# Slave.net
KiCad netlist of a schematic drawn in Altium Designer
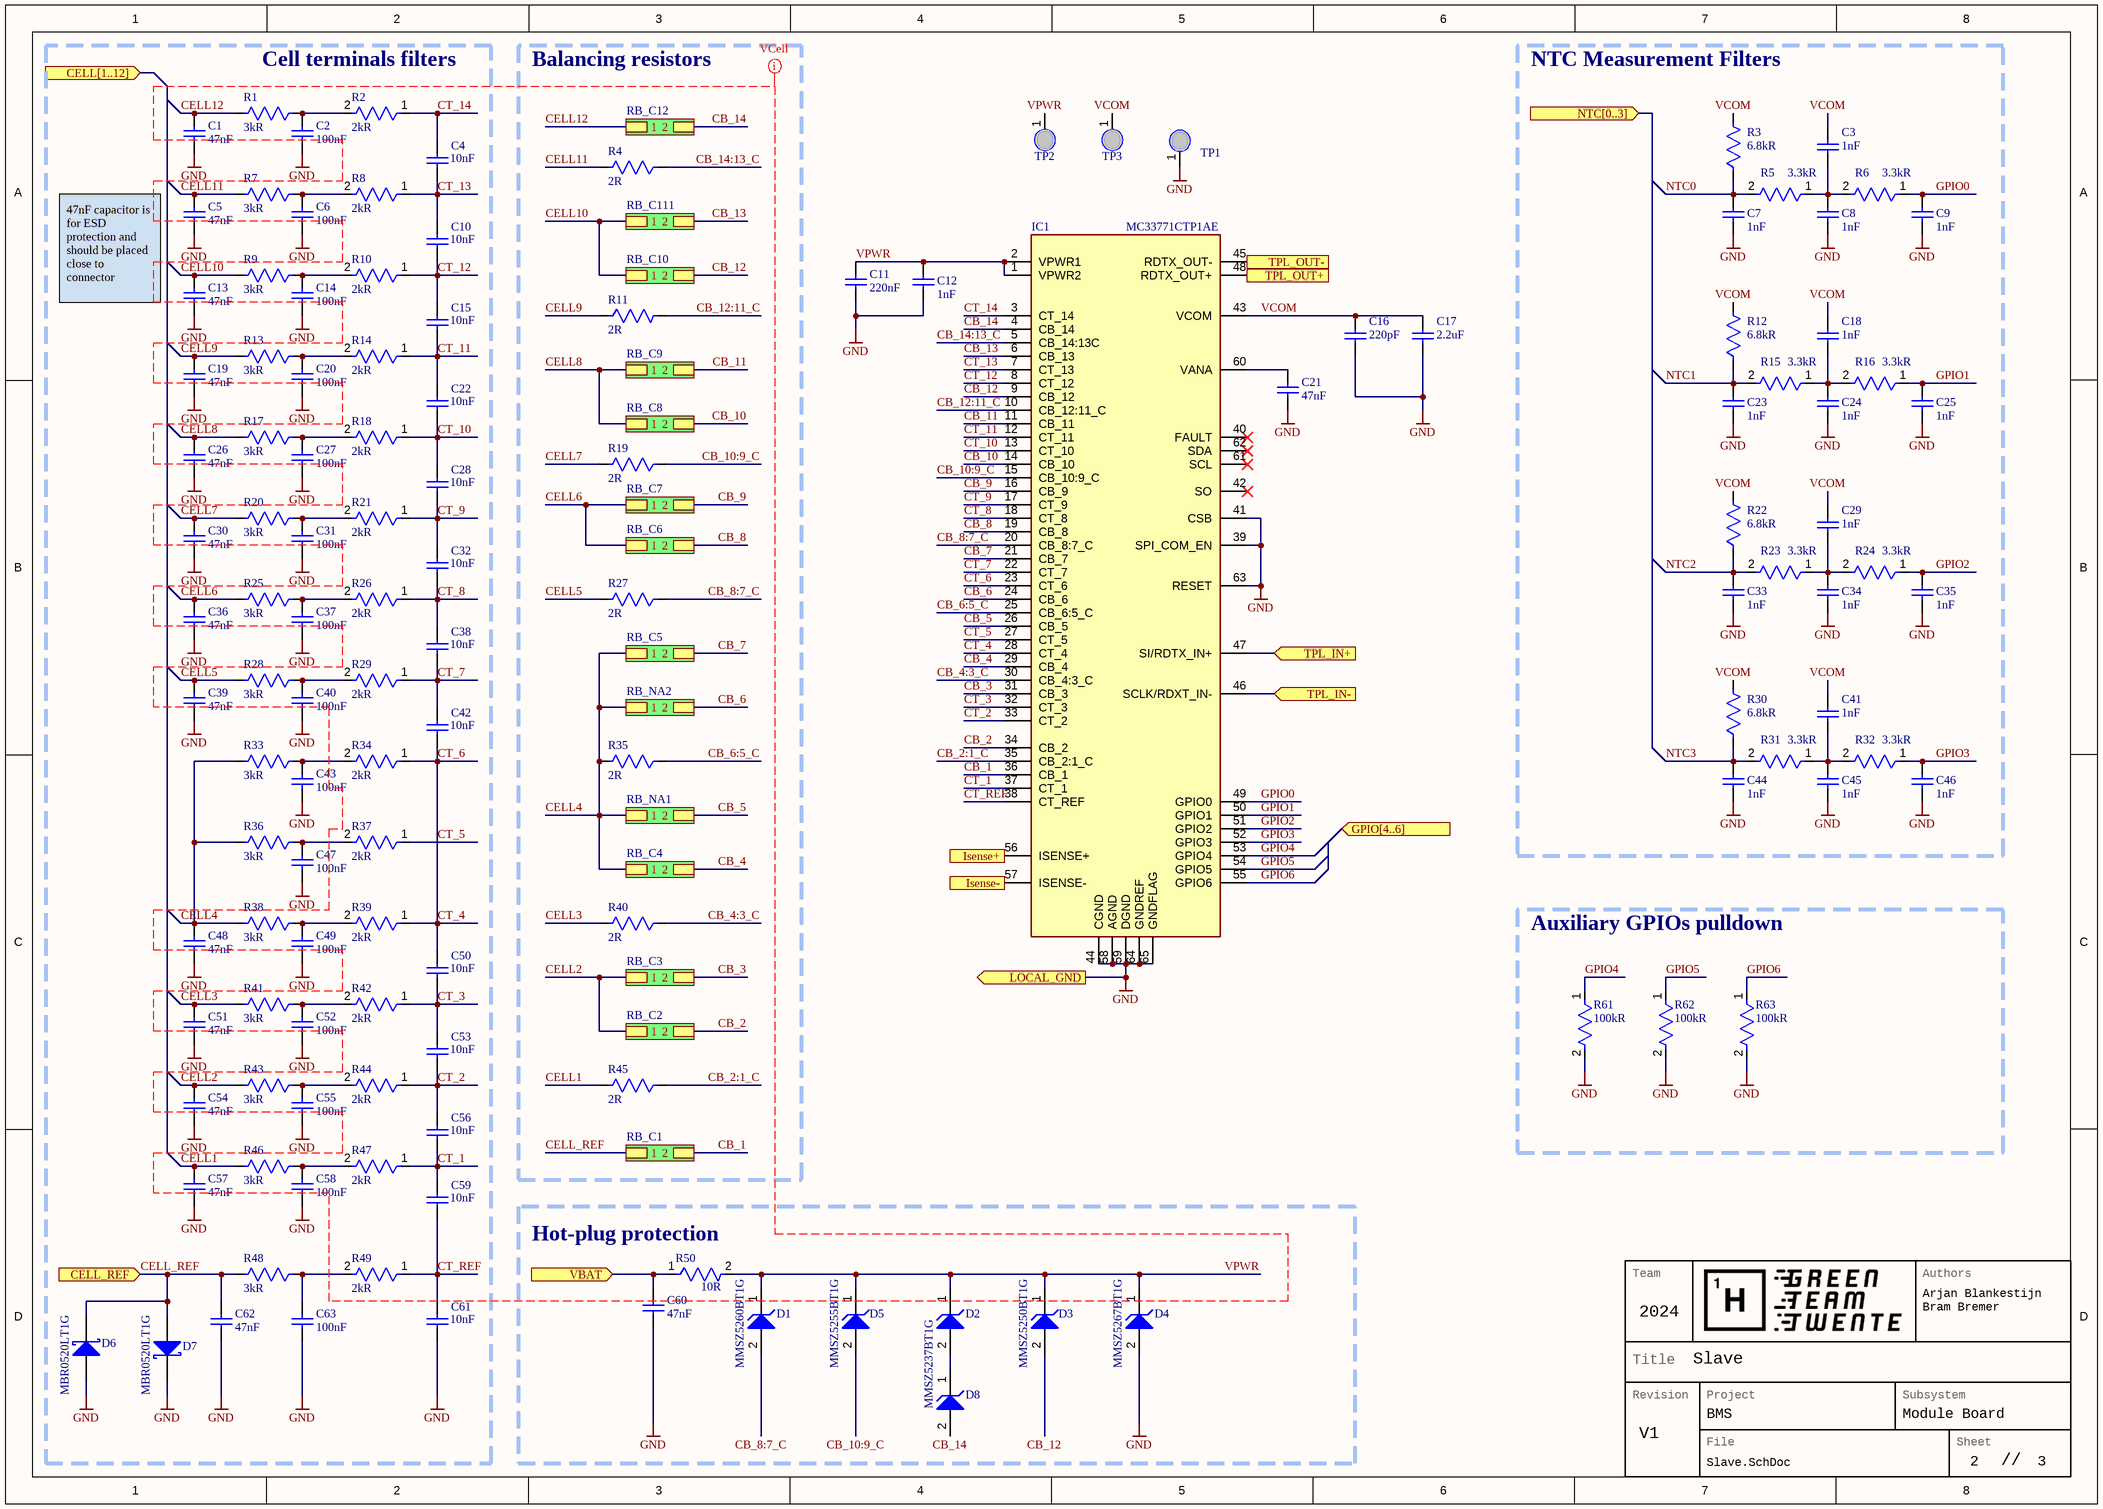
[diagram p0: Slave.SchDoc]

(export (version "E")
  (design (tool "Eeschema 10.0.6"))
  (components
    (comp (ref "C1")
      (value "47nF")
      (footprint "WCAP-CSGP_0603_L1.6W0.8H0.8_Reflow")
      (description "GTT Standard 0603 non-polarized capacitor")
      (fields (field (name "TOLERANCE") "5%") (field (name "JLCPCB PART #") "C1622"))
      (libsource (lib "Green Team Twente") (part "CAP_NONPOL_GENERIC"))
    )
    (comp (ref "C2")
      (value "100nF")
      (footprint "WCAP-CSGP_0603_L1.6W0.8H0.8_Reflow")
      (description "GTT Standard 0603 non-polarized capacitor")
      (fields (field (name "TOLERANCE") "5%") (field (name "JLCPCB PART #") "C14663"))
      (libsource (lib "Green Team Twente") (part "CAP_NONPOL_GENERIC"))
    )
    (comp (ref "C3")
      (value "1nF")
      (footprint "WCAP-CSGP_0402_L1W0.5H0.5")
      (description "GTT Standard 0402 non-polarized capacitor")
      (fields (field (name "JLCPCB PART #") "C1523") (field (name "Comment") "CAP 0402 1nF X7R"))
      (libsource (lib "Green Team Twente") (part "CAP_NONPOL_GENERIC"))
    )
    (comp (ref "C4")
      (value "10nF")
      (footprint "WCAP-CSGP_0402_L1W0.5H0.5")
      (description "GTT Standard 0402 non-polarized capacitor")
      (fields (field (name "JLCPCB PART #") "C15195") (field (name "Comment") "CAP 0402 10nF X7R"))
      (libsource (lib "Green Team Twente") (part "CAP_NONPOL_GENERIC"))
    )
    (comp (ref "C5")
      (value "47nF")
      (footprint "WCAP-CSGP_0603_L1.6W0.8H0.8_Reflow")
      (description "GTT Standard 0603 non-polarized capacitor")
      (fields (field (name "TOLERANCE") "5%") (field (name "JLCPCB PART #") "C1622"))
      (libsource (lib "Green Team Twente") (part "CAP_NONPOL_GENERIC"))
    )
    (comp (ref "C6")
      (value "100nF")
      (footprint "WCAP-CSGP_0603_L1.6W0.8H0.8_Reflow")
      (description "GTT Standard 0603 non-polarized capacitor")
      (fields (field (name "TOLERANCE") "5%") (field (name "JLCPCB PART #") "C14663"))
      (libsource (lib "Green Team Twente") (part "CAP_NONPOL_GENERIC"))
    )
    (comp (ref "C7")
      (value "1nF")
      (footprint "WCAP-CSGP_0402_L1W0.5H0.5")
      (description "GTT Standard 0402 non-polarized capacitor")
      (fields (field (name "JLCPCB PART #") "C1523") (field (name "Comment") "CAP 0402 1nF X7R"))
      (libsource (lib "Green Team Twente") (part "CAP_NONPOL_GENERIC"))
    )
    (comp (ref "C8")
      (value "1nF")
      (footprint "WCAP-CSGP_0402_L1W0.5H0.5")
      (description "GTT Standard 0402 non-polarized capacitor")
      (fields (field (name "JLCPCB PART #") "C1523") (field (name "Comment") "CAP 0402 1nF X7R"))
      (libsource (lib "Green Team Twente") (part "CAP_NONPOL_GENERIC"))
    )
    (comp (ref "C9")
      (value "1nF")
      (footprint "WCAP-CSGP_0402_L1W0.5H0.5")
      (description "GTT Standard 0402 non-polarized capacitor")
      (fields (field (name "JLCPCB PART #") "C1523") (field (name "Comment") "CAP 0402 1nF X7R"))
      (libsource (lib "Green Team Twente") (part "CAP_NONPOL_GENERIC"))
    )
    (comp (ref "C10")
      (value "10nF")
      (footprint "WCAP-CSGP_0402_L1W0.5H0.5")
      (description "GTT Standard 0402 non-polarized capacitor")
      (fields (field (name "JLCPCB PART #") "C15195") (field (name "Comment") "CAP 0402 10nF X7R"))
      (libsource (lib "Green Team Twente") (part "CAP_NONPOL_GENERIC"))
    )
    (comp (ref "C11")
      (value "220nF")
      (footprint "WCAP-CSGP_0603_L1.6W0.8H0.8_Reflow")
      (description "GTT Standard 0603 non-polarized capacitor")
      (fields (field (name "TOLERANCE") "5%") (field (name "JLCPCB PART #") "C21120"))
      (libsource (lib "Green Team Twente") (part "CAP_NONPOL_GENERIC"))
    )
    (comp (ref "C12")
      (value "1nF")
      (footprint "WCAP-CSGP_0402_L1W0.5H0.5")
      (description "GTT Standard 0402 non-polarized capacitor")
      (fields (field (name "JLCPCB PART #") "C1523") (field (name "Comment") "CAP 0402 1nF X7R"))
      (libsource (lib "Green Team Twente") (part "CAP_NONPOL_GENERIC"))
    )
    (comp (ref "C13")
      (value "47nF")
      (footprint "WCAP-CSGP_0603_L1.6W0.8H0.8_Reflow")
      (description "GTT Standard 0603 non-polarized capacitor")
      (fields (field (name "TOLERANCE") "5%") (field (name "JLCPCB PART #") "C1622"))
      (libsource (lib "Green Team Twente") (part "CAP_NONPOL_GENERIC"))
    )
    (comp (ref "C14")
      (value "100nF")
      (footprint "WCAP-CSGP_0603_L1.6W0.8H0.8_Reflow")
      (description "GTT Standard 0603 non-polarized capacitor")
      (fields (field (name "TOLERANCE") "5%") (field (name "JLCPCB PART #") "C14663"))
      (libsource (lib "Green Team Twente") (part "CAP_NONPOL_GENERIC"))
    )
    (comp (ref "C15")
      (value "10nF")
      (footprint "WCAP-CSGP_0402_L1W0.5H0.5")
      (description "GTT Standard 0402 non-polarized capacitor")
      (fields (field (name "JLCPCB PART #") "C15195") (field (name "Comment") "CAP 0402 10nF X7R"))
      (libsource (lib "Green Team Twente") (part "CAP_NONPOL_GENERIC"))
    )
    (comp (ref "C16")
      (value "220pF")
      (footprint "WCAP-CSGP_0402_L1W0.5H0.5")
      (description "GTT Standard 0402 non-polarized capacitor")
      (fields (field (name "JLCPCB PART #") "C1530") (field (name "Comment") "CAP 0402 220pF X7R"))
      (libsource (lib "Green Team Twente") (part "CAP_NONPOL_GENERIC"))
    )
    (comp (ref "C17")
      (value "2.2uF")
      (footprint "WCAP-CSGP_0603_L1.6W0.8H0.8_Reflow")
      (description "GTT Standard 0603 non-polarized capacitor")
      (fields (field (name "TOLERANCE") "5%") (field (name "JLCPCB PART #") "C23630"))
      (libsource (lib "Green Team Twente") (part "CAP_NONPOL_GENERIC"))
    )
    (comp (ref "C18")
      (value "1nF")
      (footprint "WCAP-CSGP_0402_L1W0.5H0.5")
      (description "GTT Standard 0402 non-polarized capacitor")
      (fields (field (name "JLCPCB PART #") "C1523") (field (name "Comment") "CAP 0402 1nF X7R"))
      (libsource (lib "Green Team Twente") (part "CAP_NONPOL_GENERIC"))
    )
    (comp (ref "C19")
      (value "47nF")
      (footprint "WCAP-CSGP_0603_L1.6W0.8H0.8_Reflow")
      (description "GTT Standard 0603 non-polarized capacitor")
      (fields (field (name "TOLERANCE") "5%") (field (name "JLCPCB PART #") "C1622"))
      (libsource (lib "Green Team Twente") (part "CAP_NONPOL_GENERIC"))
    )
    (comp (ref "C20")
      (value "100nF")
      (footprint "WCAP-CSGP_0603_L1.6W0.8H0.8_Reflow")
      (description "GTT Standard 0603 non-polarized capacitor")
      (fields (field (name "TOLERANCE") "5%") (field (name "JLCPCB PART #") "C14663"))
      (libsource (lib "Green Team Twente") (part "CAP_NONPOL_GENERIC"))
    )
    (comp (ref "C21")
      (value "47nF")
      (footprint "WCAP-CSGP_0603_L1.6W0.8H0.8_Reflow")
      (description "GTT Standard 0603 non-polarized capacitor")
      (fields (field (name "TOLERANCE") "5%") (field (name "JLCPCB PART #") "C1622"))
      (libsource (lib "Green Team Twente") (part "CAP_NONPOL_GENERIC"))
    )
    (comp (ref "C22")
      (value "10nF")
      (footprint "WCAP-CSGP_0402_L1W0.5H0.5")
      (description "GTT Standard 0402 non-polarized capacitor")
      (fields (field (name "JLCPCB PART #") "C15195") (field (name "Comment") "CAP 0402 10nF X7R"))
      (libsource (lib "Green Team Twente") (part "CAP_NONPOL_GENERIC"))
    )
    (comp (ref "C23")
      (value "1nF")
      (footprint "WCAP-CSGP_0402_L1W0.5H0.5")
      (description "GTT Standard 0402 non-polarized capacitor")
      (fields (field (name "JLCPCB PART #") "C1523") (field (name "Comment") "CAP 0402 1nF X7R"))
      (libsource (lib "Green Team Twente") (part "CAP_NONPOL_GENERIC"))
    )
    (comp (ref "C24")
      (value "1nF")
      (footprint "WCAP-CSGP_0402_L1W0.5H0.5")
      (description "GTT Standard 0402 non-polarized capacitor")
      (fields (field (name "JLCPCB PART #") "C1523") (field (name "Comment") "CAP 0402 1nF X7R"))
      (libsource (lib "Green Team Twente") (part "CAP_NONPOL_GENERIC"))
    )
    (comp (ref "C25")
      (value "1nF")
      (footprint "WCAP-CSGP_0402_L1W0.5H0.5")
      (description "GTT Standard 0402 non-polarized capacitor")
      (fields (field (name "JLCPCB PART #") "C1523") (field (name "Comment") "CAP 0402 1nF X7R"))
      (libsource (lib "Green Team Twente") (part "CAP_NONPOL_GENERIC"))
    )
    (comp (ref "C26")
      (value "47nF")
      (footprint "WCAP-CSGP_0603_L1.6W0.8H0.8_Reflow")
      (description "GTT Standard 0603 non-polarized capacitor")
      (fields (field (name "TOLERANCE") "5%") (field (name "JLCPCB PART #") "C1622"))
      (libsource (lib "Green Team Twente") (part "CAP_NONPOL_GENERIC"))
    )
    (comp (ref "C27")
      (value "100nF")
      (footprint "WCAP-CSGP_0603_L1.6W0.8H0.8_Reflow")
      (description "GTT Standard 0603 non-polarized capacitor")
      (fields (field (name "TOLERANCE") "5%") (field (name "JLCPCB PART #") "C14663"))
      (libsource (lib "Green Team Twente") (part "CAP_NONPOL_GENERIC"))
    )
    (comp (ref "C28")
      (value "10nF")
      (footprint "WCAP-CSGP_0402_L1W0.5H0.5")
      (description "GTT Standard 0402 non-polarized capacitor")
      (fields (field (name "JLCPCB PART #") "C15195") (field (name "Comment") "CAP 0402 10nF X7R"))
      (libsource (lib "Green Team Twente") (part "CAP_NONPOL_GENERIC"))
    )
    (comp (ref "C29")
      (value "1nF")
      (footprint "WCAP-CSGP_0402_L1W0.5H0.5")
      (description "GTT Standard 0402 non-polarized capacitor")
      (fields (field (name "JLCPCB PART #") "C1523") (field (name "Comment") "CAP 0402 1nF X7R"))
      (libsource (lib "Green Team Twente") (part "CAP_NONPOL_GENERIC"))
    )
    (comp (ref "C30")
      (value "47nF")
      (footprint "WCAP-CSGP_0603_L1.6W0.8H0.8_Reflow")
      (description "GTT Standard 0603 non-polarized capacitor")
      (fields (field (name "TOLERANCE") "5%") (field (name "JLCPCB PART #") "C1622"))
      (libsource (lib "Green Team Twente") (part "CAP_NONPOL_GENERIC"))
    )
    (comp (ref "C31")
      (value "100nF")
      (footprint "WCAP-CSGP_0603_L1.6W0.8H0.8_Reflow")
      (description "GTT Standard 0603 non-polarized capacitor")
      (fields (field (name "TOLERANCE") "5%") (field (name "JLCPCB PART #") "C14663"))
      (libsource (lib "Green Team Twente") (part "CAP_NONPOL_GENERIC"))
    )
    (comp (ref "C32")
      (value "10nF")
      (footprint "WCAP-CSGP_0402_L1W0.5H0.5")
      (description "GTT Standard 0402 non-polarized capacitor")
      (fields (field (name "JLCPCB PART #") "C15195") (field (name "Comment") "CAP 0402 10nF X7R"))
      (libsource (lib "Green Team Twente") (part "CAP_NONPOL_GENERIC"))
    )
    (comp (ref "C33")
      (value "1nF")
      (footprint "WCAP-CSGP_0402_L1W0.5H0.5")
      (description "GTT Standard 0402 non-polarized capacitor")
      (fields (field (name "JLCPCB PART #") "C1523") (field (name "Comment") "CAP 0402 1nF X7R"))
      (libsource (lib "Green Team Twente") (part "CAP_NONPOL_GENERIC"))
    )
    (comp (ref "C34")
      (value "1nF")
      (footprint "WCAP-CSGP_0402_L1W0.5H0.5")
      (description "GTT Standard 0402 non-polarized capacitor")
      (fields (field (name "JLCPCB PART #") "C1523") (field (name "Comment") "CAP 0402 1nF X7R"))
      (libsource (lib "Green Team Twente") (part "CAP_NONPOL_GENERIC"))
    )
    (comp (ref "C35")
      (value "1nF")
      (footprint "WCAP-CSGP_0402_L1W0.5H0.5")
      (description "GTT Standard 0402 non-polarized capacitor")
      (fields (field (name "JLCPCB PART #") "C1523") (field (name "Comment") "CAP 0402 1nF X7R"))
      (libsource (lib "Green Team Twente") (part "CAP_NONPOL_GENERIC"))
    )
    (comp (ref "C36")
      (value "47nF")
      (footprint "WCAP-CSGP_0603_L1.6W0.8H0.8_Reflow")
      (description "GTT Standard 0603 non-polarized capacitor")
      (fields (field (name "TOLERANCE") "5%") (field (name "JLCPCB PART #") "C1622"))
      (libsource (lib "Green Team Twente") (part "CAP_NONPOL_GENERIC"))
    )
    (comp (ref "C37")
      (value "100nF")
      (footprint "WCAP-CSGP_0603_L1.6W0.8H0.8_Reflow")
      (description "GTT Standard 0603 non-polarized capacitor")
      (fields (field (name "TOLERANCE") "5%") (field (name "JLCPCB PART #") "C14663"))
      (libsource (lib "Green Team Twente") (part "CAP_NONPOL_GENERIC"))
    )
    (comp (ref "C38")
      (value "10nF")
      (footprint "WCAP-CSGP_0402_L1W0.5H0.5")
      (description "GTT Standard 0402 non-polarized capacitor")
      (fields (field (name "JLCPCB PART #") "C15195") (field (name "Comment") "CAP 0402 10nF X7R"))
      (libsource (lib "Green Team Twente") (part "CAP_NONPOL_GENERIC"))
    )
    (comp (ref "C39")
      (value "47nF")
      (footprint "WCAP-CSGP_0603_L1.6W0.8H0.8_Reflow")
      (description "GTT Standard 0603 non-polarized capacitor")
      (fields (field (name "TOLERANCE") "5%") (field (name "JLCPCB PART #") "C1622"))
      (libsource (lib "Green Team Twente") (part "CAP_NONPOL_GENERIC"))
    )
    (comp (ref "C40")
      (value "100nF")
      (footprint "WCAP-CSGP_0603_L1.6W0.8H0.8_Reflow")
      (description "GTT Standard 0603 non-polarized capacitor")
      (fields (field (name "TOLERANCE") "5%") (field (name "JLCPCB PART #") "C14663"))
      (libsource (lib "Green Team Twente") (part "CAP_NONPOL_GENERIC"))
    )
    (comp (ref "C41")
      (value "1nF")
      (footprint "WCAP-CSGP_0402_L1W0.5H0.5")
      (description "GTT Standard 0402 non-polarized capacitor")
      (fields (field (name "JLCPCB PART #") "C1523") (field (name "Comment") "CAP 0402 1nF X7R"))
      (libsource (lib "Green Team Twente") (part "CAP_NONPOL_GENERIC"))
    )
    (comp (ref "C42")
      (value "10nF")
      (footprint "WCAP-CSGP_0402_L1W0.5H0.5")
      (description "GTT Standard 0402 non-polarized capacitor")
      (fields (field (name "JLCPCB PART #") "C15195") (field (name "Comment") "CAP 0402 10nF X7R"))
      (libsource (lib "Green Team Twente") (part "CAP_NONPOL_GENERIC"))
    )
    (comp (ref "C43")
      (value "100nF")
      (footprint "WCAP-CSGP_0603_L1.6W0.8H0.8_Reflow")
      (description "GTT Standard 0603 non-polarized capacitor")
      (fields (field (name "TOLERANCE") "5%") (field (name "JLCPCB PART #") "C14663"))
      (libsource (lib "Green Team Twente") (part "CAP_NONPOL_GENERIC"))
    )
    (comp (ref "C44")
      (value "1nF")
      (footprint "WCAP-CSGP_0402_L1W0.5H0.5")
      (description "GTT Standard 0402 non-polarized capacitor")
      (fields (field (name "JLCPCB PART #") "C1523") (field (name "Comment") "CAP 0402 1nF X7R"))
      (libsource (lib "Green Team Twente") (part "CAP_NONPOL_GENERIC"))
    )
    (comp (ref "C45")
      (value "1nF")
      (footprint "WCAP-CSGP_0402_L1W0.5H0.5")
      (description "GTT Standard 0402 non-polarized capacitor")
      (fields (field (name "JLCPCB PART #") "C1523") (field (name "Comment") "CAP 0402 1nF X7R"))
      (libsource (lib "Green Team Twente") (part "CAP_NONPOL_GENERIC"))
    )
    (comp (ref "C46")
      (value "1nF")
      (footprint "WCAP-CSGP_0402_L1W0.5H0.5")
      (description "GTT Standard 0402 non-polarized capacitor")
      (fields (field (name "JLCPCB PART #") "C1523") (field (name "Comment") "CAP 0402 1nF X7R"))
      (libsource (lib "Green Team Twente") (part "CAP_NONPOL_GENERIC"))
    )
    (comp (ref "C47")
      (value "100nF")
      (footprint "WCAP-CSGP_0603_L1.6W0.8H0.8_Reflow")
      (description "GTT Standard 0603 non-polarized capacitor")
      (fields (field (name "TOLERANCE") "5%") (field (name "JLCPCB PART #") "C14663"))
      (libsource (lib "Green Team Twente") (part "CAP_NONPOL_GENERIC"))
    )
    (comp (ref "C48")
      (value "47nF")
      (footprint "WCAP-CSGP_0603_L1.6W0.8H0.8_Reflow")
      (description "GTT Standard 0603 non-polarized capacitor")
      (fields (field (name "TOLERANCE") "5%") (field (name "JLCPCB PART #") "C1622"))
      (libsource (lib "Green Team Twente") (part "CAP_NONPOL_GENERIC"))
    )
    (comp (ref "C49")
      (value "100nF")
      (footprint "WCAP-CSGP_0603_L1.6W0.8H0.8_Reflow")
      (description "GTT Standard 0603 non-polarized capacitor")
      (fields (field (name "TOLERANCE") "5%") (field (name "JLCPCB PART #") "C14663"))
      (libsource (lib "Green Team Twente") (part "CAP_NONPOL_GENERIC"))
    )
    (comp (ref "C50")
      (value "10nF")
      (footprint "WCAP-CSGP_0402_L1W0.5H0.5")
      (description "GTT Standard 0402 non-polarized capacitor")
      (fields (field (name "JLCPCB PART #") "C15195") (field (name "Comment") "CAP 0402 10nF X7R"))
      (libsource (lib "Green Team Twente") (part "CAP_NONPOL_GENERIC"))
    )
    (comp (ref "C51")
      (value "47nF")
      (footprint "WCAP-CSGP_0603_L1.6W0.8H0.8_Reflow")
      (description "GTT Standard 0603 non-polarized capacitor")
      (fields (field (name "TOLERANCE") "5%") (field (name "JLCPCB PART #") "C1622"))
      (libsource (lib "Green Team Twente") (part "CAP_NONPOL_GENERIC"))
    )
    (comp (ref "C52")
      (value "100nF")
      (footprint "WCAP-CSGP_0603_L1.6W0.8H0.8_Reflow")
      (description "GTT Standard 0603 non-polarized capacitor")
      (fields (field (name "TOLERANCE") "5%") (field (name "JLCPCB PART #") "C14663"))
      (libsource (lib "Green Team Twente") (part "CAP_NONPOL_GENERIC"))
    )
    (comp (ref "C53")
      (value "10nF")
      (footprint "WCAP-CSGP_0402_L1W0.5H0.5")
      (description "GTT Standard 0402 non-polarized capacitor")
      (fields (field (name "JLCPCB PART #") "C15195") (field (name "Comment") "CAP 0402 10nF X7R"))
      (libsource (lib "Green Team Twente") (part "CAP_NONPOL_GENERIC"))
    )
    (comp (ref "C54")
      (value "47nF")
      (footprint "WCAP-CSGP_0603_L1.6W0.8H0.8_Reflow")
      (description "GTT Standard 0603 non-polarized capacitor")
      (fields (field (name "TOLERANCE") "5%") (field (name "JLCPCB PART #") "C1622"))
      (libsource (lib "Green Team Twente") (part "CAP_NONPOL_GENERIC"))
    )
    (comp (ref "C55")
      (value "100nF")
      (footprint "WCAP-CSGP_0603_L1.6W0.8H0.8_Reflow")
      (description "GTT Standard 0603 non-polarized capacitor")
      (fields (field (name "TOLERANCE") "5%") (field (name "JLCPCB PART #") "C14663"))
      (libsource (lib "Green Team Twente") (part "CAP_NONPOL_GENERIC"))
    )
    (comp (ref "C56")
      (value "10nF")
      (footprint "WCAP-CSGP_0402_L1W0.5H0.5")
      (description "GTT Standard 0402 non-polarized capacitor")
      (fields (field (name "JLCPCB PART #") "C15195") (field (name "Comment") "CAP 0402 10nF X7R"))
      (libsource (lib "Green Team Twente") (part "CAP_NONPOL_GENERIC"))
    )
    (comp (ref "C57")
      (value "47nF")
      (footprint "WCAP-CSGP_0603_L1.6W0.8H0.8_Reflow")
      (description "GTT Standard 0603 non-polarized capacitor")
      (fields (field (name "TOLERANCE") "5%") (field (name "JLCPCB PART #") "C1622"))
      (libsource (lib "Green Team Twente") (part "CAP_NONPOL_GENERIC"))
    )
    (comp (ref "C58")
      (value "100nF")
      (footprint "WCAP-CSGP_0603_L1.6W0.8H0.8_Reflow")
      (description "GTT Standard 0603 non-polarized capacitor")
      (fields (field (name "TOLERANCE") "5%") (field (name "JLCPCB PART #") "C14663"))
      (libsource (lib "Green Team Twente") (part "CAP_NONPOL_GENERIC"))
    )
    (comp (ref "C59")
      (value "10nF")
      (footprint "WCAP-CSGP_0402_L1W0.5H0.5")
      (description "GTT Standard 0402 non-polarized capacitor")
      (fields (field (name "JLCPCB PART #") "C15195") (field (name "Comment") "CAP 0402 10nF X7R"))
      (libsource (lib "Green Team Twente") (part "CAP_NONPOL_GENERIC"))
    )
    (comp (ref "C60")
      (value "47nF")
      (footprint "WCAP-CSGP_0603_L1.6W0.8H0.8_Reflow")
      (description "GTT Standard 0603 non-polarized capacitor")
      (fields (field (name "TOLERANCE") "5%") (field (name "JLCPCB PART #") "C1622"))
      (libsource (lib "Green Team Twente") (part "CAP_NONPOL_GENERIC"))
    )
    (comp (ref "C61")
      (value "10nF")
      (footprint "WCAP-CSGP_0402_L1W0.5H0.5")
      (description "GTT Standard 0402 non-polarized capacitor")
      (fields (field (name "JLCPCB PART #") "C15195") (field (name "Comment") "CAP 0402 10nF X7R"))
      (libsource (lib "Green Team Twente") (part "CAP_NONPOL_GENERIC"))
    )
    (comp (ref "C62")
      (value "47nF")
      (footprint "WCAP-CSGP_0603_L1.6W0.8H0.8_Reflow")
      (description "GTT Standard 0603 non-polarized capacitor")
      (fields (field (name "TOLERANCE") "5%") (field (name "JLCPCB PART #") "C1622"))
      (libsource (lib "Green Team Twente") (part "CAP_NONPOL_GENERIC"))
    )
    (comp (ref "C63")
      (value "100nF")
      (footprint "WCAP-CSGP_0603_L1.6W0.8H0.8_Reflow")
      (description "GTT Standard 0603 non-polarized capacitor")
      (fields (field (name "TOLERANCE") "5%") (field (name "JLCPCB PART #") "C14663"))
      (libsource (lib "Green Team Twente") (part "CAP_NONPOL_GENERIC"))
    )
    (comp (ref "D1")
      (value "MMSZ5260BT1G")
      (footprint "ONSC-SOD-123-2-425-04_V")
      (description "Zener Voltage Regulator, 500 mW, 2-Pin SOD-123, Pb-Free, Tape and Reel")
      (fields (field (name "MANUFACTURER") "On Semiconductor"))
      (libsource (lib "Altium Content Vault") (part "ONSC-K1A2-2"))
    )
    (comp (ref "D2")
      (value "MMSZ5237BT1G")
      (footprint "ONSC-SOD-123-2-425-04_V")
      (description "Zener Voltage Regulator, 500 mW, 2-Pin SOD-123, Pb-Free, Tape and Reel")
      (fields (field (name "MANUFACTURER") "On Semiconductor"))
      (libsource (lib "Altium Content Vault") (part "ONSC-K1A2-2"))
    )
    (comp (ref "D3")
      (value "MMSZ5250BT1G")
      (footprint "ONSC-SOD-123-2-425-04_V")
      (description "Zener Voltage Regulator, 500 mW, 2-Pin SOD-123, Pb-Free, Tape and Reel")
      (fields (field (name "MANUFACTURER") "On Semiconductor") (field (name "JLCPCB PART #") "C94386"))
      (libsource (lib "Altium Content Vault") (part "ONSC-K1A2-2"))
    )
    (comp (ref "D4")
      (value "MMSZ5267BT1G")
      (footprint "ONSC-SOD-123-2-425-04_V")
      (description "Zener Voltage Regulator, 500 mW, 2-Pin SOD-123, Pb-Free, Tape and Reel")
      (fields (field (name "MANUFACTURER") "On Semiconductor") (field (name "JLCPCB PART #") "C80160"))
      (libsource (lib "Altium Content Vault") (part "ONSC-K1A2-2"))
    )
    (comp (ref "D5")
      (value "MMSZ5255BT1G")
      (footprint "ONSC-SOD-123-2-425-04_V")
      (description "MMSZ5255BT1 Series 500 mW 10 mA 28 V SMT Zener Voltage Regulator - SOD-123")
      (fields (field (name "PARTNUMBER") "MMSZ5250BT1G") (field (name "MANUFACTURER") "On Semiconductor"))
      (libsource (lib "Altium Content Vault") (part "ONSC-K1A2-2"))
    )
    (comp (ref "D6")
      (value "MBR0520LT1G")
      (footprint "ONSC-SOD-123-2-425-04_V")
      (description "Schottky Power Rectifier, 20 V, 5.5 A, -65 to 125 degC, 2-Pin SMD, RoHS, Tape and Reel")
      (fields (field (name "MANUFACTURER") "ON Semiconductor"))
      (libsource (lib "Green Team Twente") (part "DSKY-AK-2"))
    )
    (comp (ref "D7")
      (value "MBR0520LT1G")
      (footprint "ONSC-SOD-123-2-425-04_V")
      (description "Schottky Power Rectifier, 20 V, 5.5 A, -65 to 125 degC, 2-Pin SMD, RoHS, Tape and Reel")
      (fields (field (name "MANUFACTURER") "ON Semiconductor"))
      (libsource (lib "Green Team Twente") (part "DSKY-AK-2"))
    )
    (comp (ref "D8")
      (value "MMSZ5237BT1G")
      (footprint "ONSC-SOD-123-2-425-04_V")
      (description "Zener Voltage Regulator, 500 mW, 2-Pin SOD-123, Pb-Free, Tape and Reel")
      (fields (field (name "MANUFACTURER") "On Semiconductor"))
      (libsource (lib "Altium Content Vault") (part "ONSC-K1A2-2"))
    )
    (comp (ref "IC1")
      (value "MC33771CTP1AE")
      (footprint "QFP50P1200X1200X160-65N")
      (description "Integrated Circuit")
      (fields (field (name "MOUSER PART NUMBER") "771-MC33771CTP1AE"))
      (libsource (lib "Green Team Twente") (part "MC33771CTP1AE"))
    )
    (comp (ref "R1")
      (value "3kR")
      (footprint "RES_SM0603_YAGEORC_N")
      (description "GTT Standard 0603 Resistor")
      (fields (field (name "POWER") "62.5mW") (field (name "TOLERANCE") "1%"))
      (libsource (lib "") (part "RES_GENERIC_1"))
    )
    (comp (ref "R2")
      (value "2kR")
      (footprint "FP0402")
      (description "GTT Standard 0402 Resistor")
      (fields (field (name "TOLERANCE") "1%") (field (name "POWER") "62.5mW"))
      (libsource (lib "Green Team Twente") (part "RES_GENERIC"))
    )
    (comp (ref "R3")
      (value "6.8kR")
      (footprint "RES_SM0603_YAGEORC_N")
      (description "GTT Standard 0603 Resistor")
      (fields (field (name "POWER") "62.5mW") (field (name "TOLERANCE") "1%"))
      (libsource (lib "") (part "RES_GENERIC_1"))
    )
    (comp (ref "R4")
      (value "2R")
      (footprint "RES_SM0603_YAGEORC_N")
      (description "GTT Standard 0603 Resistor")
      (fields (field (name "POWER") "100mW") (field (name "TOLERANCE") "1%"))
      (libsource (lib "") (part "RES_GENERIC_1"))
    )
    (comp (ref "R5")
      (value "3.3kR")
      (footprint "FP0402")
      (description "GTT Standard 0402 Resistor")
      (fields (field (name "TOLERANCE") "1%") (field (name "POWER") "62.5mW"))
      (libsource (lib "Green Team Twente") (part "RES_GENERIC"))
    )
    (comp (ref "R6")
      (value "3.3kR")
      (footprint "FP0402")
      (description "GTT Standard 0402 Resistor")
      (fields (field (name "TOLERANCE") "1%") (field (name "POWER") "62.5mW"))
      (libsource (lib "Green Team Twente") (part "RES_GENERIC"))
    )
    (comp (ref "R7")
      (value "3kR")
      (footprint "RES_SM0603_YAGEORC_N")
      (description "GTT Standard 0603 Resistor")
      (fields (field (name "POWER") "62.5mW") (field (name "TOLERANCE") "1%"))
      (libsource (lib "") (part "RES_GENERIC_1"))
    )
    (comp (ref "R8")
      (value "2kR")
      (footprint "FP0402")
      (description "GTT Standard 0402 Resistor")
      (fields (field (name "TOLERANCE") "1%") (field (name "POWER") "62.5mW"))
      (libsource (lib "Green Team Twente") (part "RES_GENERIC"))
    )
    (comp (ref "R9")
      (value "3kR")
      (footprint "RES_SM0603_YAGEORC_N")
      (description "GTT Standard 0603 Resistor")
      (fields (field (name "POWER") "62.5mW") (field (name "TOLERANCE") "1%"))
      (libsource (lib "") (part "RES_GENERIC_1"))
    )
    (comp (ref "R10")
      (value "2kR")
      (footprint "FP0402")
      (description "GTT Standard 0402 Resistor")
      (fields (field (name "TOLERANCE") "1%") (field (name "POWER") "62.5mW"))
      (libsource (lib "Green Team Twente") (part "RES_GENERIC"))
    )
    (comp (ref "R11")
      (value "2R")
      (footprint "RES_SM0603_YAGEORC_N")
      (description "GTT Standard 0603 Resistor")
      (fields (field (name "POWER") "100mW") (field (name "TOLERANCE") "1%"))
      (libsource (lib "") (part "RES_GENERIC_1"))
    )
    (comp (ref "R12")
      (value "6.8kR")
      (footprint "RES_SM0603_YAGEORC_N")
      (description "GTT Standard 0603 Resistor")
      (fields (field (name "POWER") "62.5mW") (field (name "TOLERANCE") "1%"))
      (libsource (lib "") (part "RES_GENERIC_1"))
    )
    (comp (ref "R13")
      (value "3kR")
      (footprint "RES_SM0603_YAGEORC_N")
      (description "GTT Standard 0603 Resistor")
      (fields (field (name "POWER") "62.5mW") (field (name "TOLERANCE") "1%"))
      (libsource (lib "") (part "RES_GENERIC_1"))
    )
    (comp (ref "R14")
      (value "2kR")
      (footprint "FP0402")
      (description "GTT Standard 0402 Resistor")
      (fields (field (name "TOLERANCE") "1%") (field (name "POWER") "62.5mW"))
      (libsource (lib "Green Team Twente") (part "RES_GENERIC"))
    )
    (comp (ref "R15")
      (value "3.3kR")
      (footprint "FP0402")
      (description "GTT Standard 0402 Resistor")
      (fields (field (name "TOLERANCE") "1%") (field (name "POWER") "62.5mW"))
      (libsource (lib "Green Team Twente") (part "RES_GENERIC"))
    )
    (comp (ref "R16")
      (value "3.3kR")
      (footprint "FP0402")
      (description "GTT Standard 0402 Resistor")
      (fields (field (name "TOLERANCE") "1%") (field (name "POWER") "62.5mW"))
      (libsource (lib "Green Team Twente") (part "RES_GENERIC"))
    )
    (comp (ref "R17")
      (value "3kR")
      (footprint "RES_SM0603_YAGEORC_N")
      (description "GTT Standard 0603 Resistor")
      (fields (field (name "POWER") "62.5mW") (field (name "TOLERANCE") "1%"))
      (libsource (lib "") (part "RES_GENERIC_1"))
    )
    (comp (ref "R18")
      (value "2kR")
      (footprint "FP0402")
      (description "GTT Standard 0402 Resistor")
      (fields (field (name "TOLERANCE") "1%") (field (name "POWER") "62.5mW"))
      (libsource (lib "Green Team Twente") (part "RES_GENERIC"))
    )
    (comp (ref "R19")
      (value "2R")
      (footprint "RES_SM0603_YAGEORC_N")
      (description "GTT Standard 0603 Resistor")
      (fields (field (name "POWER") "100mW") (field (name "TOLERANCE") "1%"))
      (libsource (lib "") (part "RES_GENERIC_1"))
    )
    (comp (ref "R20")
      (value "3kR")
      (footprint "RES_SM0603_YAGEORC_N")
      (description "GTT Standard 0603 Resistor")
      (fields (field (name "POWER") "62.5mW") (field (name "TOLERANCE") "1%"))
      (libsource (lib "") (part "RES_GENERIC_1"))
    )
    (comp (ref "R21")
      (value "2kR")
      (footprint "FP0402")
      (description "GTT Standard 0402 Resistor")
      (fields (field (name "TOLERANCE") "1%") (field (name "POWER") "62.5mW"))
      (libsource (lib "Green Team Twente") (part "RES_GENERIC"))
    )
    (comp (ref "R22")
      (value "6.8kR")
      (footprint "RES_SM0603_YAGEORC_N")
      (description "GTT Standard 0603 Resistor")
      (fields (field (name "POWER") "62.5mW") (field (name "TOLERANCE") "1%"))
      (libsource (lib "") (part "RES_GENERIC_1"))
    )
    (comp (ref "R23")
      (value "3.3kR")
      (footprint "FP0402")
      (description "GTT Standard 0402 Resistor")
      (fields (field (name "TOLERANCE") "1%") (field (name "POWER") "62.5mW"))
      (libsource (lib "Green Team Twente") (part "RES_GENERIC"))
    )
    (comp (ref "R24")
      (value "3.3kR")
      (footprint "FP0402")
      (description "GTT Standard 0402 Resistor")
      (fields (field (name "TOLERANCE") "1%") (field (name "POWER") "62.5mW"))
      (libsource (lib "Green Team Twente") (part "RES_GENERIC"))
    )
    (comp (ref "R25")
      (value "3kR")
      (footprint "RES_SM0603_YAGEORC_N")
      (description "GTT Standard 0603 Resistor")
      (fields (field (name "POWER") "62.5mW") (field (name "TOLERANCE") "1%"))
      (libsource (lib "") (part "RES_GENERIC_1"))
    )
    (comp (ref "R26")
      (value "2kR")
      (footprint "FP0402")
      (description "GTT Standard 0402 Resistor")
      (fields (field (name "TOLERANCE") "1%") (field (name "POWER") "62.5mW"))
      (libsource (lib "Green Team Twente") (part "RES_GENERIC"))
    )
    (comp (ref "R27")
      (value "2R")
      (footprint "RES_SM0603_YAGEORC_N")
      (description "GTT Standard 0603 Resistor")
      (fields (field (name "POWER") "100mW") (field (name "TOLERANCE") "1%"))
      (libsource (lib "") (part "RES_GENERIC_1"))
    )
    (comp (ref "R28")
      (value "3kR")
      (footprint "RES_SM0603_YAGEORC_N")
      (description "GTT Standard 0603 Resistor")
      (fields (field (name "POWER") "62.5mW") (field (name "TOLERANCE") "1%"))
      (libsource (lib "") (part "RES_GENERIC_1"))
    )
    (comp (ref "R29")
      (value "2kR")
      (footprint "FP0402")
      (description "GTT Standard 0402 Resistor")
      (fields (field (name "TOLERANCE") "1%") (field (name "POWER") "62.5mW"))
      (libsource (lib "Green Team Twente") (part "RES_GENERIC"))
    )
    (comp (ref "R30")
      (value "6.8kR")
      (footprint "RES_SM0603_YAGEORC_N")
      (description "GTT Standard 0603 Resistor")
      (fields (field (name "POWER") "62.5mW") (field (name "TOLERANCE") "1%"))
      (libsource (lib "") (part "RES_GENERIC_1"))
    )
    (comp (ref "R31")
      (value "3.3kR")
      (footprint "FP0402")
      (description "GTT Standard 0402 Resistor")
      (fields (field (name "TOLERANCE") "1%") (field (name "POWER") "62.5mW"))
      (libsource (lib "Green Team Twente") (part "RES_GENERIC"))
    )
    (comp (ref "R32")
      (value "3.3kR")
      (footprint "FP0402")
      (description "GTT Standard 0402 Resistor")
      (fields (field (name "TOLERANCE") "1%") (field (name "POWER") "62.5mW"))
      (libsource (lib "Green Team Twente") (part "RES_GENERIC"))
    )
    (comp (ref "R33")
      (value "3kR")
      (footprint "RES_SM0603_YAGEORC_N")
      (description "GTT Standard 0603 Resistor")
      (fields (field (name "POWER") "62.5mW") (field (name "TOLERANCE") "1%"))
      (libsource (lib "") (part "RES_GENERIC_1"))
    )
    (comp (ref "R34")
      (value "2kR")
      (footprint "FP0402")
      (description "GTT Standard 0402 Resistor")
      (fields (field (name "TOLERANCE") "1%") (field (name "POWER") "62.5mW"))
      (libsource (lib "Green Team Twente") (part "RES_GENERIC"))
    )
    (comp (ref "R35")
      (value "2R")
      (footprint "RES_SM0603_YAGEORC_N")
      (description "GTT Standard 0603 Resistor")
      (fields (field (name "POWER") "100mW") (field (name "TOLERANCE") "1%"))
      (libsource (lib "") (part "RES_GENERIC_1"))
    )
    (comp (ref "R36")
      (value "3kR")
      (footprint "RES_SM0603_YAGEORC_N")
      (description "GTT Standard 0603 Resistor")
      (fields (field (name "POWER") "62.5mW") (field (name "TOLERANCE") "1%"))
      (libsource (lib "") (part "RES_GENERIC_1"))
    )
    (comp (ref "R37")
      (value "2kR")
      (footprint "FP0402")
      (description "GTT Standard 0402 Resistor")
      (fields (field (name "TOLERANCE") "1%") (field (name "POWER") "62.5mW"))
      (libsource (lib "Green Team Twente") (part "RES_GENERIC"))
    )
    (comp (ref "R38")
      (value "3kR")
      (footprint "RES_SM0603_YAGEORC_N")
      (description "GTT Standard 0603 Resistor")
      (fields (field (name "POWER") "62.5mW") (field (name "TOLERANCE") "1%"))
      (libsource (lib "") (part "RES_GENERIC_1"))
    )
    (comp (ref "R39")
      (value "2kR")
      (footprint "FP0402")
      (description "GTT Standard 0402 Resistor")
      (fields (field (name "TOLERANCE") "1%") (field (name "POWER") "62.5mW"))
      (libsource (lib "Green Team Twente") (part "RES_GENERIC"))
    )
    (comp (ref "R40")
      (value "2R")
      (footprint "RES_SM0603_YAGEORC_N")
      (description "GTT Standard 0603 Resistor")
      (fields (field (name "POWER") "100mW") (field (name "TOLERANCE") "1%"))
      (libsource (lib "") (part "RES_GENERIC_1"))
    )
    (comp (ref "R41")
      (value "3kR")
      (footprint "RES_SM0603_YAGEORC_N")
      (description "GTT Standard 0603 Resistor")
      (fields (field (name "POWER") "62.5mW") (field (name "TOLERANCE") "1%"))
      (libsource (lib "") (part "RES_GENERIC_1"))
    )
    (comp (ref "R42")
      (value "2kR")
      (footprint "FP0402")
      (description "GTT Standard 0402 Resistor")
      (fields (field (name "TOLERANCE") "1%") (field (name "POWER") "62.5mW"))
      (libsource (lib "Green Team Twente") (part "RES_GENERIC"))
    )
    (comp (ref "R43")
      (value "3kR")
      (footprint "RES_SM0603_YAGEORC_N")
      (description "GTT Standard 0603 Resistor")
      (fields (field (name "POWER") "62.5mW") (field (name "TOLERANCE") "1%"))
      (libsource (lib "") (part "RES_GENERIC_1"))
    )
    (comp (ref "R44")
      (value "2kR")
      (footprint "FP0402")
      (description "GTT Standard 0402 Resistor")
      (fields (field (name "TOLERANCE") "1%") (field (name "POWER") "62.5mW"))
      (libsource (lib "Green Team Twente") (part "RES_GENERIC"))
    )
    (comp (ref "R45")
      (value "2R")
      (footprint "RES_SM0603_YAGEORC_N")
      (description "GTT Standard 0603 Resistor")
      (fields (field (name "POWER") "100mW") (field (name "TOLERANCE") "1%"))
      (libsource (lib "") (part "RES_GENERIC_1"))
    )
    (comp (ref "R46")
      (value "3kR")
      (footprint "RES_SM0603_YAGEORC_N")
      (description "GTT Standard 0603 Resistor")
      (fields (field (name "POWER") "62.5mW") (field (name "TOLERANCE") "1%"))
      (libsource (lib "") (part "RES_GENERIC_1"))
    )
    (comp (ref "R47")
      (value "2kR")
      (footprint "FP0402")
      (description "GTT Standard 0402 Resistor")
      (fields (field (name "TOLERANCE") "1%") (field (name "POWER") "62.5mW"))
      (libsource (lib "Green Team Twente") (part "RES_GENERIC"))
    )
    (comp (ref "R48")
      (value "3kR")
      (footprint "RES_SM0603_YAGEORC_N")
      (description "GTT Standard 0603 Resistor")
      (fields (field (name "POWER") "62.5mW") (field (name "TOLERANCE") "1%"))
      (libsource (lib "") (part "RES_GENERIC_1"))
    )
    (comp (ref "R49")
      (value "2kR")
      (footprint "FP0402")
      (description "GTT Standard 0402 Resistor")
      (fields (field (name "TOLERANCE") "1%") (field (name "POWER") "62.5mW"))
      (libsource (lib "Green Team Twente") (part "RES_GENERIC"))
    )
    (comp (ref "R50")
      (value "10R")
      (footprint "RES_SM1206_YAGEORC_N")
      (description "GTT Standard 1206 Resistor")
      (fields (field (name "TOLERANCE") "1%") (field (name "POWER") "250mW"))
      (libsource (lib "Green Team Twente") (part "RES_GENERIC"))
    )
    (comp (ref "R61")
      (value "100kR")
      (footprint "FP0402")
      (description "GTT Standard 0402 Resistor")
      (fields (field (name "TOLERANCE") "1%") (field (name "POWER") "62.5mW"))
      (libsource (lib "Green Team Twente") (part "RES_GENERIC"))
    )
    (comp (ref "R62")
      (value "100kR")
      (footprint "FP0402")
      (description "GTT Standard 0402 Resistor")
      (fields (field (name "TOLERANCE") "1%") (field (name "POWER") "62.5mW"))
      (libsource (lib "Green Team Twente") (part "RES_GENERIC"))
    )
    (comp (ref "R63")
      (value "100kR")
      (footprint "FP0402")
      (description "GTT Standard 0402 Resistor")
      (fields (field (name "TOLERANCE") "1%") (field (name "POWER") "62.5mW"))
      (libsource (lib "Green Team Twente") (part "RES_GENERIC"))
    )
    (comp (ref "TP1")
      (value "GTT_ProbeerPunt")
      (footprint "GTT_ProbeerPuntFP")
      (libsource (lib "Green Team Twente") (part "Test Point"))
    )
    (comp (ref "TP2")
      (value "GTT_ProbeerPunt")
      (footprint "GTT_ProbeerPuntFP")
      (libsource (lib "Green Team Twente") (part "Test Point"))
    )
    (comp (ref "TP3")
      (value "GTT_ProbeerPunt")
      (footprint "GTT_ProbeerPuntFP")
      (libsource (lib "Green Team Twente") (part "Test Point"))
    )
  )
  (nets
    (net (code "1") (name "/CB_1") (class "Default")
      (node (ref "IC1") (pin "36") (pinfunction "CB_1_36") (pintype "passive"))
    )
    (net (code "2") (name "/CB_2") (class "Default")
      (node (ref "IC1") (pin "34") (pinfunction "CB_2_34") (pintype "passive"))
    )
    (net (code "3") (name "/CB_2:1_C") (class "Default")
      (node (ref "IC1") (pin "35") (pinfunction "CB_2:1_C_35") (pintype "passive"))
      (node (ref "R45") (pin "1") (pinfunction "1_1") (pintype "passive"))
    )
    (net (code "4") (name "/CB_3") (class "Default")
      (node (ref "IC1") (pin "31") (pinfunction "CB_3_31") (pintype "passive"))
    )
    (net (code "5") (name "/CB_4") (class "Default")
      (node (ref "IC1") (pin "29") (pinfunction "CB_4_29") (pintype "passive"))
    )
    (net (code "6") (name "/CB_4:3_C") (class "Default")
      (node (ref "IC1") (pin "30") (pinfunction "CB_4:3_C_30") (pintype "passive"))
      (node (ref "R40") (pin "1") (pinfunction "1_1") (pintype "passive"))
    )
    (net (code "7") (name "/CB_5") (class "Default")
      (node (ref "IC1") (pin "26") (pinfunction "CB_5_26") (pintype "passive"))
    )
    (net (code "8") (name "/CB_6") (class "Default")
      (node (ref "IC1") (pin "24") (pinfunction "CB_6_24") (pintype "passive"))
    )
    (net (code "9") (name "/CB_6:5_C") (class "Default")
      (node (ref "IC1") (pin "25") (pinfunction "CB_6:5_C_25") (pintype "passive"))
      (node (ref "R35") (pin "1") (pinfunction "1_1") (pintype "passive"))
    )
    (net (code "10") (name "/CB_7") (class "Default")
      (node (ref "IC1") (pin "21") (pinfunction "CB_7_21") (pintype "passive"))
    )
    (net (code "11") (name "/CB_8") (class "Default")
      (node (ref "IC1") (pin "19") (pinfunction "CB_8_19") (pintype "passive"))
    )
    (net (code "12") (name "/CB_8:7_C") (class "Default")
      (node (ref "D1") (pin "2") (pinfunction "A_2") (pintype "passive"))
      (node (ref "IC1") (pin "20") (pinfunction "CB_8:7_C_20") (pintype "passive"))
      (node (ref "R27") (pin "1") (pinfunction "1_1") (pintype "passive"))
    )
    (net (code "13") (name "/CB_9") (class "Default")
      (node (ref "IC1") (pin "16") (pinfunction "CB_9_16") (pintype "passive"))
    )
    (net (code "14") (name "/CB_10") (class "Default")
      (node (ref "IC1") (pin "14") (pinfunction "CB_10_14") (pintype "passive"))
    )
    (net (code "15") (name "/CB_10:9_C") (class "Default")
      (node (ref "D5") (pin "2") (pinfunction "A_2") (pintype "passive"))
      (node (ref "IC1") (pin "15") (pinfunction "CB_10:9_C_15") (pintype "passive"))
      (node (ref "R19") (pin "1") (pinfunction "1_1") (pintype "passive"))
    )
    (net (code "16") (name "/CB_11") (class "Default")
      (node (ref "IC1") (pin "11") (pinfunction "CB_11_11") (pintype "passive"))
    )
    (net (code "17") (name "/CB_12") (class "Default")
      (node (ref "D3") (pin "2") (pinfunction "A_2") (pintype "passive"))
      (node (ref "IC1") (pin "9") (pinfunction "CB_12_9") (pintype "passive"))
    )
    (net (code "18") (name "/CB_12:11_C") (class "Default")
      (node (ref "IC1") (pin "10") (pinfunction "CB_12:11_C_10") (pintype "passive"))
      (node (ref "R11") (pin "2") (pinfunction "2_2") (pintype "passive"))
    )
    (net (code "19") (name "/CB_13") (class "Default")
      (node (ref "IC1") (pin "6") (pinfunction "CB_13_6") (pintype "passive"))
    )
    (net (code "20") (name "/CB_14") (class "Default")
      (node (ref "D8") (pin "2") (pinfunction "A_2") (pintype "passive"))
      (node (ref "IC1") (pin "4") (pinfunction "CB_14_4") (pintype "passive"))
    )
    (net (code "21") (name "/CB_14:13_C") (class "Default")
      (node (ref "IC1") (pin "5") (pinfunction "CB_14:13C_5") (pintype "passive"))
      (node (ref "R4") (pin "1") (pinfunction "1_1") (pintype "passive"))
    )
    (net (code "22") (name "/CELL1") (class "Default")
      (node (ref "C57") (pin "2") (pinfunction "2_2") (pintype "passive"))
      (node (ref "R45") (pin "2") (pinfunction "2_2") (pintype "passive"))
      (node (ref "R46") (pin "2") (pinfunction "2_2") (pintype "passive"))
    )
    (net (code "23") (name "/CELL2") (class "Default")
      (node (ref "C54") (pin "2") (pinfunction "2_2") (pintype "passive"))
      (node (ref "R43") (pin "2") (pinfunction "2_2") (pintype "passive"))
    )
    (net (code "24") (name "/CELL3") (class "Default")
      (node (ref "C51") (pin "2") (pinfunction "2_2") (pintype "passive"))
      (node (ref "R40") (pin "2") (pinfunction "2_2") (pintype "passive"))
      (node (ref "R41") (pin "2") (pinfunction "2_2") (pintype "passive"))
    )
    (net (code "25") (name "/CELL4") (class "Default")
      (node (ref "C48") (pin "2") (pinfunction "2_2") (pintype "passive"))
      (node (ref "R33") (pin "2") (pinfunction "2_2") (pintype "passive"))
      (node (ref "R35") (pin "2") (pinfunction "2_2") (pintype "passive"))
      (node (ref "R36") (pin "2") (pinfunction "2_2") (pintype "passive"))
      (node (ref "R38") (pin "2") (pinfunction "2_2") (pintype "passive"))
    )
    (net (code "26") (name "/CELL5") (class "Default")
      (node (ref "C39") (pin "2") (pinfunction "2_2") (pintype "passive"))
      (node (ref "R27") (pin "2") (pinfunction "2_2") (pintype "passive"))
      (node (ref "R28") (pin "2") (pinfunction "2_2") (pintype "passive"))
    )
    (net (code "27") (name "/CELL6") (class "Default")
      (node (ref "C36") (pin "2") (pinfunction "2_2") (pintype "passive"))
      (node (ref "R25") (pin "2") (pinfunction "2_2") (pintype "passive"))
    )
    (net (code "28") (name "/CELL7") (class "Default")
      (node (ref "C30") (pin "2") (pinfunction "2_2") (pintype "passive"))
      (node (ref "R19") (pin "2") (pinfunction "2_2") (pintype "passive"))
      (node (ref "R20") (pin "2") (pinfunction "2_2") (pintype "passive"))
    )
    (net (code "29") (name "/CELL8") (class "Default")
      (node (ref "C26") (pin "2") (pinfunction "2_2") (pintype "passive"))
      (node (ref "R17") (pin "2") (pinfunction "2_2") (pintype "passive"))
    )
    (net (code "30") (name "/CELL9") (class "Default")
      (node (ref "C19") (pin "2") (pinfunction "2_2") (pintype "passive"))
      (node (ref "R11") (pin "1") (pinfunction "1_1") (pintype "passive"))
      (node (ref "R13") (pin "2") (pinfunction "2_2") (pintype "passive"))
    )
    (net (code "31") (name "/CELL10") (class "Default")
      (node (ref "C13") (pin "2") (pinfunction "2_2") (pintype "passive"))
      (node (ref "R9") (pin "2") (pinfunction "2_2") (pintype "passive"))
    )
    (net (code "32") (name "/CELL11") (class "Default")
      (node (ref "C5") (pin "2") (pinfunction "2_2") (pintype "passive"))
      (node (ref "R4") (pin "2") (pinfunction "2_2") (pintype "passive"))
      (node (ref "R7") (pin "2") (pinfunction "2_2") (pintype "passive"))
    )
    (net (code "33") (name "/CELL12") (class "Default")
      (node (ref "C1") (pin "2") (pinfunction "2_2") (pintype "passive"))
      (node (ref "R1") (pin "2") (pinfunction "2_2") (pintype "passive"))
    )
    (net (code "35") (name "/CELL_REF") (class "Default")
      (node (ref "C62") (pin "2") (pinfunction "2_2") (pintype "passive"))
      (node (ref "D6") (pin "2") (pinfunction "K_2") (pintype "passive"))
      (node (ref "D7") (pin "1") (pinfunction "A_1") (pintype "passive"))
      (node (ref "R48") (pin "2") (pinfunction "2_2") (pintype "passive"))
    )
    (net (code "36") (name "/CT_1") (class "Default")
      (node (ref "C56") (pin "1") (pinfunction "1_1") (pintype "passive"))
      (node (ref "C59") (pin "2") (pinfunction "2_2") (pintype "passive"))
      (node (ref "IC1") (pin "37") (pinfunction "CT_1_37") (pintype "passive"))
      (node (ref "R47") (pin "1") (pinfunction "1_1") (pintype "passive"))
    )
    (net (code "37") (name "/CT_2") (class "Default")
      (node (ref "C53") (pin "1") (pinfunction "1_1") (pintype "passive"))
      (node (ref "C56") (pin "2") (pinfunction "2_2") (pintype "passive"))
      (node (ref "IC1") (pin "33") (pinfunction "CT_2_33") (pintype "passive"))
      (node (ref "R44") (pin "1") (pinfunction "1_1") (pintype "passive"))
    )
    (net (code "38") (name "/CT_3") (class "Default")
      (node (ref "C50") (pin "1") (pinfunction "1_1") (pintype "passive"))
      (node (ref "C53") (pin "2") (pinfunction "2_2") (pintype "passive"))
      (node (ref "IC1") (pin "32") (pinfunction "CT_3_32") (pintype "passive"))
      (node (ref "R42") (pin "1") (pinfunction "1_1") (pintype "passive"))
    )
    (net (code "39") (name "/CT_4") (class "Default")
      (node (ref "C42") (pin "1") (pinfunction "1_1") (pintype "passive"))
      (node (ref "C50") (pin "2") (pinfunction "2_2") (pintype "passive"))
      (node (ref "IC1") (pin "23") (pinfunction "CT_6_23") (pintype "passive"))
      (node (ref "IC1") (pin "27") (pinfunction "CT_5_27") (pintype "passive"))
      (node (ref "IC1") (pin "28") (pinfunction "CT_4_28") (pintype "passive"))
      (node (ref "R34") (pin "1") (pinfunction "1_1") (pintype "passive"))
      (node (ref "R37") (pin "1") (pinfunction "1_1") (pintype "passive"))
      (node (ref "R39") (pin "1") (pinfunction "1_1") (pintype "passive"))
    )
    (net (code "40") (name "/CT_7") (class "Default")
      (node (ref "C38") (pin "1") (pinfunction "1_1") (pintype "passive"))
      (node (ref "C42") (pin "2") (pinfunction "2_2") (pintype "passive"))
      (node (ref "IC1") (pin "22") (pinfunction "CT_7_22") (pintype "passive"))
      (node (ref "R29") (pin "1") (pinfunction "1_1") (pintype "passive"))
    )
    (net (code "41") (name "/CT_8") (class "Default")
      (node (ref "C32") (pin "1") (pinfunction "1_1") (pintype "passive"))
      (node (ref "C38") (pin "2") (pinfunction "2_2") (pintype "passive"))
      (node (ref "IC1") (pin "18") (pinfunction "CT_8_18") (pintype "passive"))
      (node (ref "R26") (pin "1") (pinfunction "1_1") (pintype "passive"))
    )
    (net (code "42") (name "/CT_9") (class "Default")
      (node (ref "C28") (pin "1") (pinfunction "1_1") (pintype "passive"))
      (node (ref "C32") (pin "2") (pinfunction "2_2") (pintype "passive"))
      (node (ref "IC1") (pin "17") (pinfunction "CT_9_17") (pintype "passive"))
      (node (ref "R21") (pin "1") (pinfunction "1_1") (pintype "passive"))
    )
    (net (code "43") (name "/CT_10") (class "Default")
      (node (ref "C22") (pin "1") (pinfunction "1_1") (pintype "passive"))
      (node (ref "C28") (pin "2") (pinfunction "2_2") (pintype "passive"))
      (node (ref "IC1") (pin "13") (pinfunction "CT_10_13") (pintype "passive"))
      (node (ref "R18") (pin "1") (pinfunction "1_1") (pintype "passive"))
    )
    (net (code "44") (name "/CT_11") (class "Default")
      (node (ref "C15") (pin "1") (pinfunction "1_1") (pintype "passive"))
      (node (ref "C22") (pin "2") (pinfunction "2_2") (pintype "passive"))
      (node (ref "IC1") (pin "12") (pinfunction "CT_11_12") (pintype "passive"))
      (node (ref "R14") (pin "1") (pinfunction "1_1") (pintype "passive"))
    )
    (net (code "45") (name "/CT_12") (class "Default")
      (node (ref "C10") (pin "1") (pinfunction "1_1") (pintype "passive"))
      (node (ref "C15") (pin "2") (pinfunction "2_2") (pintype "passive"))
      (node (ref "IC1") (pin "8") (pinfunction "CT_12_8") (pintype "passive"))
      (node (ref "R10") (pin "1") (pinfunction "1_1") (pintype "passive"))
    )
    (net (code "46") (name "/CT_13") (class "Default")
      (node (ref "C10") (pin "2") (pinfunction "2_2") (pintype "passive"))
      (node (ref "C4") (pin "1") (pinfunction "1_1") (pintype "passive"))
      (node (ref "IC1") (pin "7") (pinfunction "CT_13_7") (pintype "passive"))
      (node (ref "R8") (pin "1") (pinfunction "1_1") (pintype "passive"))
    )
    (net (code "47") (name "/CT_14") (class "Default")
      (node (ref "C4") (pin "2") (pinfunction "2_2") (pintype "passive"))
      (node (ref "IC1") (pin "3") (pinfunction "CT_14_3") (pintype "passive"))
      (node (ref "R2") (pin "1") (pinfunction "1_1") (pintype "passive"))
    )
    (net (code "48") (name "/CT_REF") (class "Default")
      (node (ref "C59") (pin "1") (pinfunction "1_1") (pintype "passive"))
      (node (ref "C61") (pin "2") (pinfunction "2_2") (pintype "passive"))
      (node (ref "IC1") (pin "38") (pinfunction "CT_REF_38") (pintype "passive"))
      (node (ref "R49") (pin "1") (pinfunction "1_1") (pintype "passive"))
    )
    (net (code "49") (name "/GPIO0") (class "Default")
      (node (ref "C9") (pin "2") (pinfunction "2_2") (pintype "passive"))
      (node (ref "IC1") (pin "49") (pinfunction "GPIO0_49") (pintype "passive"))
      (node (ref "R6") (pin "1") (pinfunction "1_1") (pintype "passive"))
    )
    (net (code "50") (name "/GPIO1") (class "Default")
      (node (ref "C25") (pin "2") (pinfunction "2_2") (pintype "passive"))
      (node (ref "IC1") (pin "50") (pinfunction "GPIO1_50") (pintype "passive"))
      (node (ref "R16") (pin "1") (pinfunction "1_1") (pintype "passive"))
    )
    (net (code "51") (name "/GPIO2") (class "Default")
      (node (ref "C35") (pin "2") (pinfunction "2_2") (pintype "passive"))
      (node (ref "IC1") (pin "51") (pinfunction "GPIO2_51") (pintype "passive"))
      (node (ref "R24") (pin "1") (pinfunction "1_1") (pintype "passive"))
    )
    (net (code "52") (name "/GPIO3") (class "Default")
      (node (ref "C46") (pin "2") (pinfunction "2_2") (pintype "passive"))
      (node (ref "IC1") (pin "52") (pinfunction "GPIO3_52") (pintype "passive"))
      (node (ref "R32") (pin "1") (pinfunction "1_1") (pintype "passive"))
    )
    (net (code "53") (name "/GPIO4") (class "Default")
      (node (ref "IC1") (pin "53") (pinfunction "GPIO4_53") (pintype "passive"))
      (node (ref "R61") (pin "1") (pinfunction "1_1") (pintype "passive"))
    )
    (net (code "54") (name "/GPIO5") (class "Default")
      (node (ref "IC1") (pin "54") (pinfunction "GPIO5_54") (pintype "passive"))
      (node (ref "R62") (pin "1") (pinfunction "1_1") (pintype "passive"))
    )
    (net (code "55") (name "/GPIO6") (class "Default")
      (node (ref "IC1") (pin "55") (pinfunction "GPIO6_55") (pintype "passive"))
      (node (ref "R63") (pin "1") (pinfunction "1_1") (pintype "passive"))
    )
    (net (code "57") (name "/Isense+") (class "Default")
      (node (ref "IC1") (pin "56") (pinfunction "ISENSE+_56") (pintype "passive"))
    )
    (net (code "58") (name "/Isense-") (class "Default")
      (node (ref "IC1") (pin "57") (pinfunction "ISENSE-_57") (pintype "passive"))
    )
    (net (code "59") (name "/NTC0") (class "Default")
      (node (ref "C7") (pin "2") (pinfunction "2_2") (pintype "passive"))
      (node (ref "R3") (pin "1") (pinfunction "1_1") (pintype "passive"))
      (node (ref "R5") (pin "2") (pinfunction "2_2") (pintype "passive"))
    )
    (net (code "60") (name "/NTC1") (class "Default")
      (node (ref "C23") (pin "2") (pinfunction "2_2") (pintype "passive"))
      (node (ref "R12") (pin "1") (pinfunction "1_1") (pintype "passive"))
      (node (ref "R15") (pin "2") (pinfunction "2_2") (pintype "passive"))
    )
    (net (code "61") (name "/NTC2") (class "Default")
      (node (ref "C33") (pin "2") (pinfunction "2_2") (pintype "passive"))
      (node (ref "R22") (pin "1") (pinfunction "1_1") (pintype "passive"))
      (node (ref "R23") (pin "2") (pinfunction "2_2") (pintype "passive"))
    )
    (net (code "62") (name "/NTC3") (class "Default")
      (node (ref "C44") (pin "2") (pinfunction "2_2") (pintype "passive"))
      (node (ref "R30") (pin "1") (pinfunction "1_1") (pintype "passive"))
      (node (ref "R31") (pin "2") (pinfunction "2_2") (pintype "passive"))
    )
    (net (code "64") (name "/TPL_IN+") (class "Default")
      (node (ref "IC1") (pin "47") (pinfunction "SI/RDTX_IN+_47") (pintype "passive"))
    )
    (net (code "65") (name "/TPL_IN-") (class "Default")
      (node (ref "IC1") (pin "46") (pinfunction "SCLK/RDXT_IN-_46") (pintype "passive"))
    )
    (net (code "66") (name "/TPL_OUT+") (class "Default")
      (node (ref "IC1") (pin "48") (pinfunction "RDTX_OUT+_48") (pintype "passive"))
    )
    (net (code "67") (name "/TPL_OUT-") (class "Default")
      (node (ref "IC1") (pin "45") (pinfunction "RDTX_OUT-_45") (pintype "passive"))
    )
    (net (code "68") (name "/VBAT") (class "Default")
      (node (ref "C60") (pin "2") (pinfunction "2_2") (pintype "passive"))
      (node (ref "R50") (pin "1") (pinfunction "1_1") (pintype "passive"))
    )
    (net (code "69") (name "/VCOM") (class "Default")
      (node (ref "C16") (pin "2") (pinfunction "2_2") (pintype "passive"))
      (node (ref "C17") (pin "2") (pinfunction "2_2") (pintype "passive"))
      (node (ref "C18") (pin "2") (pinfunction "2_2") (pintype "passive"))
      (node (ref "C29") (pin "2") (pinfunction "2_2") (pintype "passive"))
      (node (ref "C3") (pin "2") (pinfunction "2_2") (pintype "passive"))
      (node (ref "C41") (pin "2") (pinfunction "2_2") (pintype "passive"))
      (node (ref "IC1") (pin "43") (pinfunction "VCOM_43") (pintype "passive"))
      (node (ref "R12") (pin "2") (pinfunction "2_2") (pintype "passive"))
      (node (ref "R22") (pin "2") (pinfunction "2_2") (pintype "passive"))
      (node (ref "R3") (pin "2") (pinfunction "2_2") (pintype "passive"))
      (node (ref "R30") (pin "2") (pinfunction "2_2") (pintype "passive"))
      (node (ref "TP3") (pin "1") (pinfunction "1_1") (pintype "passive"))
    )
    (net (code "70") (name "/VPWR") (class "Default")
      (node (ref "C11") (pin "2") (pinfunction "2_2") (pintype "passive"))
      (node (ref "C12") (pin "2") (pinfunction "2_2") (pintype "passive"))
      (node (ref "D1") (pin "1") (pinfunction "K_1") (pintype "passive"))
      (node (ref "D2") (pin "1") (pinfunction "K_1") (pintype "passive"))
      (node (ref "D3") (pin "1") (pinfunction "K_1") (pintype "passive"))
      (node (ref "D4") (pin "1") (pinfunction "K_1") (pintype "passive"))
      (node (ref "D5") (pin "1") (pinfunction "K_1") (pintype "passive"))
      (node (ref "IC1") (pin "1") (pinfunction "VPWR2_1") (pintype "passive"))
      (node (ref "IC1") (pin "2") (pinfunction "VPWR1_2") (pintype "passive"))
      (node (ref "R50") (pin "2") (pinfunction "2_2") (pintype "passive"))
      (node (ref "TP2") (pin "1") (pinfunction "1_1") (pintype "passive"))
    )
    (net (code "71") (name "GND") (class "Default")
      (node (ref "C1") (pin "1") (pinfunction "1_1") (pintype "passive"))
      (node (ref "C11") (pin "1") (pinfunction "1_1") (pintype "passive"))
      (node (ref "C12") (pin "1") (pinfunction "1_1") (pintype "passive"))
      (node (ref "C13") (pin "1") (pinfunction "1_1") (pintype "passive"))
      (node (ref "C14") (pin "1") (pinfunction "1_1") (pintype "passive"))
      (node (ref "C16") (pin "1") (pinfunction "1_1") (pintype "passive"))
      (node (ref "C17") (pin "1") (pinfunction "1_1") (pintype "passive"))
      (node (ref "C19") (pin "1") (pinfunction "1_1") (pintype "passive"))
      (node (ref "C2") (pin "1") (pinfunction "1_1") (pintype "passive"))
      (node (ref "C20") (pin "1") (pinfunction "1_1") (pintype "passive"))
      (node (ref "C21") (pin "1") (pinfunction "1_1") (pintype "passive"))
      (node (ref "C23") (pin "1") (pinfunction "1_1") (pintype "passive"))
      (node (ref "C24") (pin "1") (pinfunction "1_1") (pintype "passive"))
      (node (ref "C25") (pin "1") (pinfunction "1_1") (pintype "passive"))
      (node (ref "C26") (pin "1") (pinfunction "1_1") (pintype "passive"))
      (node (ref "C27") (pin "1") (pinfunction "1_1") (pintype "passive"))
      (node (ref "C30") (pin "1") (pinfunction "1_1") (pintype "passive"))
      (node (ref "C31") (pin "1") (pinfunction "1_1") (pintype "passive"))
      (node (ref "C33") (pin "1") (pinfunction "1_1") (pintype "passive"))
      (node (ref "C34") (pin "1") (pinfunction "1_1") (pintype "passive"))
      (node (ref "C35") (pin "1") (pinfunction "1_1") (pintype "passive"))
      (node (ref "C36") (pin "1") (pinfunction "1_1") (pintype "passive"))
      (node (ref "C37") (pin "1") (pinfunction "1_1") (pintype "passive"))
      (node (ref "C39") (pin "1") (pinfunction "1_1") (pintype "passive"))
      (node (ref "C40") (pin "1") (pinfunction "1_1") (pintype "passive"))
      (node (ref "C43") (pin "1") (pinfunction "1_1") (pintype "passive"))
      (node (ref "C44") (pin "1") (pinfunction "1_1") (pintype "passive"))
      (node (ref "C45") (pin "1") (pinfunction "1_1") (pintype "passive"))
      (node (ref "C46") (pin "1") (pinfunction "1_1") (pintype "passive"))
      (node (ref "C47") (pin "1") (pinfunction "1_1") (pintype "passive"))
      (node (ref "C48") (pin "1") (pinfunction "1_1") (pintype "passive"))
      (node (ref "C49") (pin "1") (pinfunction "1_1") (pintype "passive"))
      (node (ref "C5") (pin "1") (pinfunction "1_1") (pintype "passive"))
      (node (ref "C51") (pin "1") (pinfunction "1_1") (pintype "passive"))
      (node (ref "C52") (pin "1") (pinfunction "1_1") (pintype "passive"))
      (node (ref "C54") (pin "1") (pinfunction "1_1") (pintype "passive"))
      (node (ref "C55") (pin "1") (pinfunction "1_1") (pintype "passive"))
      (node (ref "C57") (pin "1") (pinfunction "1_1") (pintype "passive"))
      (node (ref "C58") (pin "1") (pinfunction "1_1") (pintype "passive"))
      (node (ref "C6") (pin "1") (pinfunction "1_1") (pintype "passive"))
      (node (ref "C60") (pin "1") (pinfunction "1_1") (pintype "passive"))
      (node (ref "C61") (pin "1") (pinfunction "1_1") (pintype "passive"))
      (node (ref "C62") (pin "1") (pinfunction "1_1") (pintype "passive"))
      (node (ref "C63") (pin "1") (pinfunction "1_1") (pintype "passive"))
      (node (ref "C7") (pin "1") (pinfunction "1_1") (pintype "passive"))
      (node (ref "C8") (pin "1") (pinfunction "1_1") (pintype "passive"))
      (node (ref "C9") (pin "1") (pinfunction "1_1") (pintype "passive"))
      (node (ref "D4") (pin "2") (pinfunction "A_2") (pintype "passive"))
      (node (ref "D6") (pin "1") (pinfunction "A_1") (pintype "passive"))
      (node (ref "D7") (pin "2") (pinfunction "K_2") (pintype "passive"))
      (node (ref "IC1") (pin "39") (pinfunction "SPI_COM_EN_39") (pintype "passive"))
      (node (ref "IC1") (pin "41") (pinfunction "CSB_41") (pintype "passive"))
      (node (ref "IC1") (pin "44") (pinfunction "CGND_44") (pintype "passive"))
      (node (ref "IC1") (pin "58") (pinfunction "AGND_58") (pintype "passive"))
      (node (ref "IC1") (pin "59") (pinfunction "DGND_59") (pintype "passive"))
      (node (ref "IC1") (pin "63") (pinfunction "RESET_63") (pintype "passive"))
      (node (ref "IC1") (pin "64") (pinfunction "GNDREF_64") (pintype "passive"))
      (node (ref "IC1") (pin "65") (pinfunction "GNDFLAG_65") (pintype "passive"))
      (node (ref "R61") (pin "2") (pinfunction "2_2") (pintype "passive"))
      (node (ref "R62") (pin "2") (pinfunction "2_2") (pintype "passive"))
      (node (ref "R63") (pin "2") (pinfunction "2_2") (pintype "passive"))
      (node (ref "TP1") (pin "1") (pinfunction "1_1") (pintype "passive"))
    )
    (net (code "72") (name "Net-(C2-Pad2)") (class "Default")
      (node (ref "C2") (pin "2") (pinfunction "2_2") (pintype "passive"))
      (node (ref "R1") (pin "1") (pinfunction "1_1") (pintype "passive"))
      (node (ref "R2") (pin "2") (pinfunction "2_2") (pintype "passive"))
    )
    (net (code "73") (name "Net-(C3-Pad1)") (class "Default")
      (node (ref "C3") (pin "1") (pinfunction "1_1") (pintype "passive"))
      (node (ref "C8") (pin "2") (pinfunction "2_2") (pintype "passive"))
      (node (ref "R5") (pin "1") (pinfunction "1_1") (pintype "passive"))
      (node (ref "R6") (pin "2") (pinfunction "2_2") (pintype "passive"))
    )
    (net (code "74") (name "Net-(C6-Pad2)") (class "Default")
      (node (ref "C6") (pin "2") (pinfunction "2_2") (pintype "passive"))
      (node (ref "R7") (pin "1") (pinfunction "1_1") (pintype "passive"))
      (node (ref "R8") (pin "2") (pinfunction "2_2") (pintype "passive"))
    )
    (net (code "75") (name "Net-(C14-Pad2)") (class "Default")
      (node (ref "C14") (pin "2") (pinfunction "2_2") (pintype "passive"))
      (node (ref "R10") (pin "2") (pinfunction "2_2") (pintype "passive"))
      (node (ref "R9") (pin "1") (pinfunction "1_1") (pintype "passive"))
    )
    (net (code "76") (name "Net-(C18-Pad1)") (class "Default")
      (node (ref "C18") (pin "1") (pinfunction "1_1") (pintype "passive"))
      (node (ref "C24") (pin "2") (pinfunction "2_2") (pintype "passive"))
      (node (ref "R15") (pin "1") (pinfunction "1_1") (pintype "passive"))
      (node (ref "R16") (pin "2") (pinfunction "2_2") (pintype "passive"))
    )
    (net (code "77") (name "Net-(C20-Pad2)") (class "Default")
      (node (ref "C20") (pin "2") (pinfunction "2_2") (pintype "passive"))
      (node (ref "R13") (pin "1") (pinfunction "1_1") (pintype "passive"))
      (node (ref "R14") (pin "2") (pinfunction "2_2") (pintype "passive"))
    )
    (net (code "78") (name "Net-(C27-Pad2)") (class "Default")
      (node (ref "C27") (pin "2") (pinfunction "2_2") (pintype "passive"))
      (node (ref "R17") (pin "1") (pinfunction "1_1") (pintype "passive"))
      (node (ref "R18") (pin "2") (pinfunction "2_2") (pintype "passive"))
    )
    (net (code "79") (name "Net-(C29-Pad1)") (class "Default")
      (node (ref "C29") (pin "1") (pinfunction "1_1") (pintype "passive"))
      (node (ref "C34") (pin "2") (pinfunction "2_2") (pintype "passive"))
      (node (ref "R23") (pin "1") (pinfunction "1_1") (pintype "passive"))
      (node (ref "R24") (pin "2") (pinfunction "2_2") (pintype "passive"))
    )
    (net (code "80") (name "Net-(C31-Pad2)") (class "Default")
      (node (ref "C31") (pin "2") (pinfunction "2_2") (pintype "passive"))
      (node (ref "R20") (pin "1") (pinfunction "1_1") (pintype "passive"))
      (node (ref "R21") (pin "2") (pinfunction "2_2") (pintype "passive"))
    )
    (net (code "81") (name "Net-(C37-Pad2)") (class "Default")
      (node (ref "C37") (pin "2") (pinfunction "2_2") (pintype "passive"))
      (node (ref "R25") (pin "1") (pinfunction "1_1") (pintype "passive"))
      (node (ref "R26") (pin "2") (pinfunction "2_2") (pintype "passive"))
    )
    (net (code "82") (name "Net-(C40-Pad2)") (class "Default")
      (node (ref "C40") (pin "2") (pinfunction "2_2") (pintype "passive"))
      (node (ref "R28") (pin "1") (pinfunction "1_1") (pintype "passive"))
      (node (ref "R29") (pin "2") (pinfunction "2_2") (pintype "passive"))
    )
    (net (code "83") (name "Net-(C41-Pad1)") (class "Default")
      (node (ref "C41") (pin "1") (pinfunction "1_1") (pintype "passive"))
      (node (ref "C45") (pin "2") (pinfunction "2_2") (pintype "passive"))
      (node (ref "R31") (pin "1") (pinfunction "1_1") (pintype "passive"))
      (node (ref "R32") (pin "2") (pinfunction "2_2") (pintype "passive"))
    )
    (net (code "84") (name "Net-(C43-Pad2)") (class "Default")
      (node (ref "C43") (pin "2") (pinfunction "2_2") (pintype "passive"))
      (node (ref "R33") (pin "1") (pinfunction "1_1") (pintype "passive"))
      (node (ref "R34") (pin "2") (pinfunction "2_2") (pintype "passive"))
    )
    (net (code "85") (name "Net-(C47-Pad2)") (class "Default")
      (node (ref "C47") (pin "2") (pinfunction "2_2") (pintype "passive"))
      (node (ref "R36") (pin "1") (pinfunction "1_1") (pintype "passive"))
      (node (ref "R37") (pin "2") (pinfunction "2_2") (pintype "passive"))
    )
    (net (code "86") (name "Net-(C49-Pad2)") (class "Default")
      (node (ref "C49") (pin "2") (pinfunction "2_2") (pintype "passive"))
      (node (ref "R38") (pin "1") (pinfunction "1_1") (pintype "passive"))
      (node (ref "R39") (pin "2") (pinfunction "2_2") (pintype "passive"))
    )
    (net (code "87") (name "Net-(C52-Pad2)") (class "Default")
      (node (ref "C52") (pin "2") (pinfunction "2_2") (pintype "passive"))
      (node (ref "R41") (pin "1") (pinfunction "1_1") (pintype "passive"))
      (node (ref "R42") (pin "2") (pinfunction "2_2") (pintype "passive"))
    )
    (net (code "88") (name "Net-(C55-Pad2)") (class "Default")
      (node (ref "C55") (pin "2") (pinfunction "2_2") (pintype "passive"))
      (node (ref "R43") (pin "1") (pinfunction "1_1") (pintype "passive"))
      (node (ref "R44") (pin "2") (pinfunction "2_2") (pintype "passive"))
    )
    (net (code "89") (name "Net-(C58-Pad2)") (class "Default")
      (node (ref "C58") (pin "2") (pinfunction "2_2") (pintype "passive"))
      (node (ref "R46") (pin "1") (pinfunction "1_1") (pintype "passive"))
      (node (ref "R47") (pin "2") (pinfunction "2_2") (pintype "passive"))
    )
    (net (code "90") (name "Net-(C63-Pad2)") (class "Default")
      (node (ref "C63") (pin "2") (pinfunction "2_2") (pintype "passive"))
      (node (ref "R48") (pin "1") (pinfunction "1_1") (pintype "passive"))
      (node (ref "R49") (pin "2") (pinfunction "2_2") (pintype "passive"))
    )
    (net (code "91") (name "Net-(D2-A)") (class "Default")
      (node (ref "D2") (pin "2") (pinfunction "A_2") (pintype "passive"))
      (node (ref "D8") (pin "1") (pinfunction "K_1") (pintype "passive"))
    )
    (net (code "92") (name "Net-(IC1-VANA)") (class "Default")
      (node (ref "C21") (pin "2") (pinfunction "2_2") (pintype "passive"))
      (node (ref "IC1") (pin "60") (pinfunction "VANA_60") (pintype "passive"))
    )
    (net (code "93") (name "unconnected-(IC1-FAULT-Pad40)") (class "Default")
      (node (ref "IC1") (pin "40") (pinfunction "FAULT_40") (pintype "passive+no_connect"))
    )
    (net (code "94") (name "unconnected-(IC1-SCL-Pad61)") (class "Default")
      (node (ref "IC1") (pin "61") (pinfunction "SCL_61") (pintype "passive+no_connect"))
    )
    (net (code "95") (name "unconnected-(IC1-SDA-Pad62)") (class "Default")
      (node (ref "IC1") (pin "62") (pinfunction "SDA_62") (pintype "passive+no_connect"))
    )
    (net (code "96") (name "unconnected-(IC1-SO-Pad42)") (class "Default")
      (node (ref "IC1") (pin "42") (pinfunction "SO_42") (pintype "passive+no_connect"))
    )
  )
)
